# Sheet2.net
KiCad netlist of a schematic drawn in Altium Designer
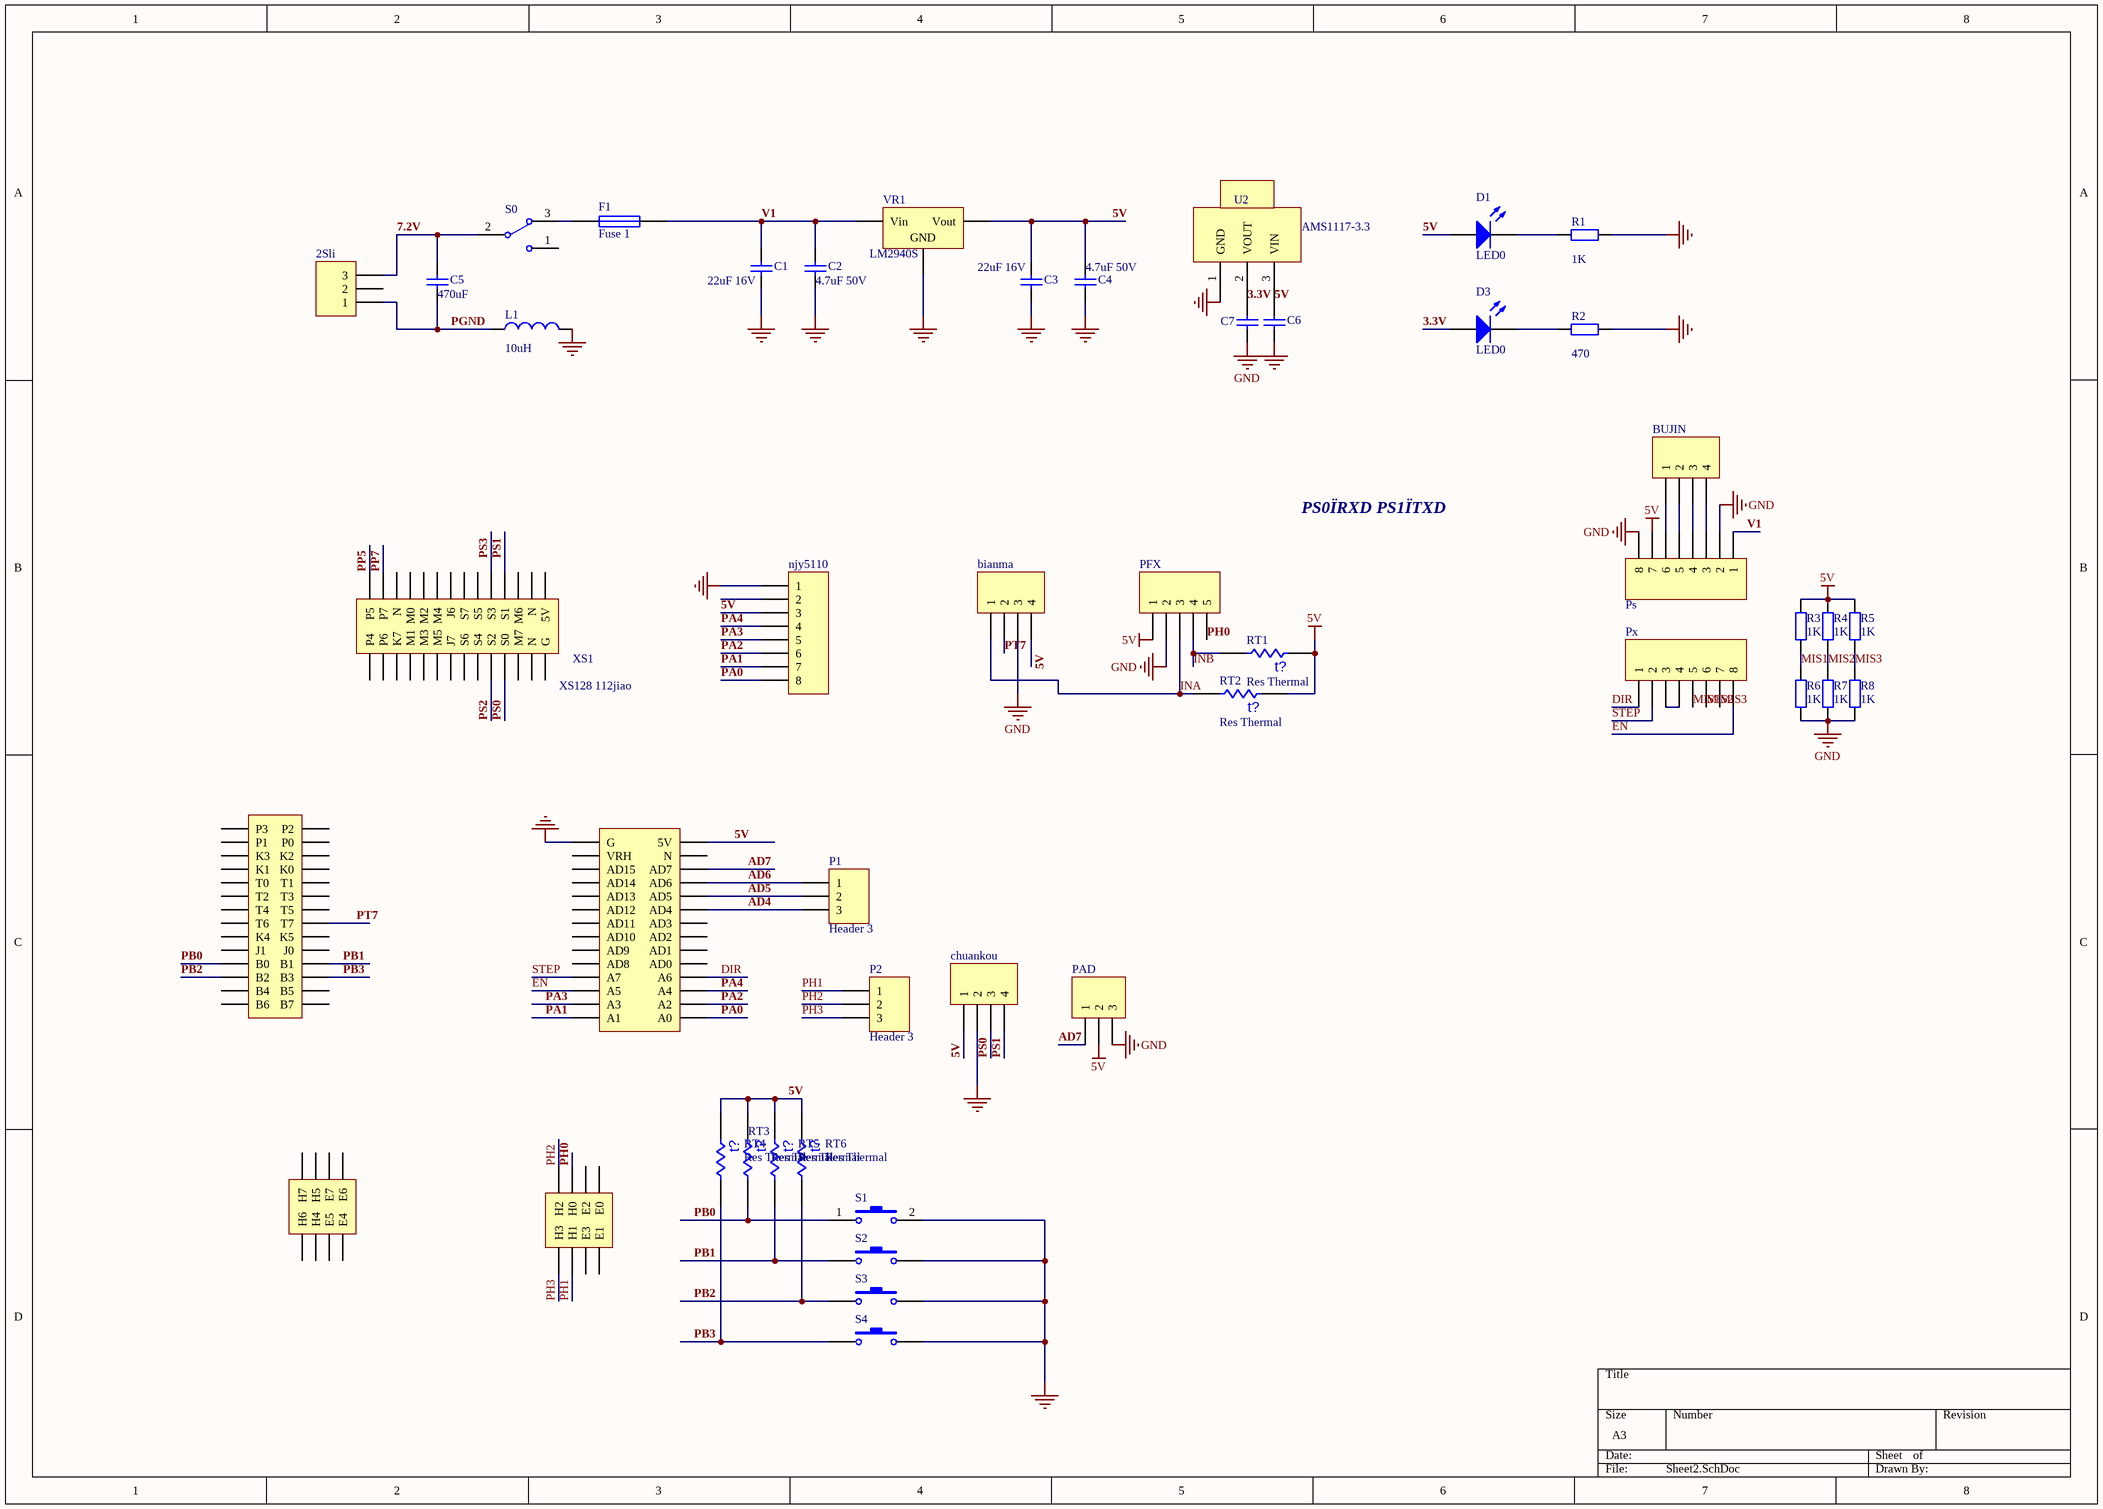
[diagram p0: Sheet2.SchDoc]

(export (version "E")
  (design (tool "Eeschema 10.0.6"))
  (components
    (comp (ref "2Sli")
      (value "Header 3")
      (footprint "HDR1X3")
      (description "Header, 3-Pin")
      (fields (field (name "PUBLISHER") "Altium Limited"))
      (libsource (lib "Miscellaneous Connectors") (part "Header 3"))
    )
    (comp (ref "bianma")
      (value "Header 4")
      (footprint "HDR1X4")
      (description "Header, 4-Pin")
      (fields (field (name "PUBLISHER") "Altium Limited"))
      (libsource (lib "Miscellaneous Connectors") (part "Header 4"))
    )
    (comp (ref "BUJIN")
      (value "Header 4")
      (footprint "HDR1X4")
      (description "Header, 4-Pin")
      (fields (field (name "PUBLISHER") "Altium Limited"))
      (libsource (lib "Miscellaneous Connectors") (part "Header 4"))
    )
    (comp (ref "C1")
      (value "22uF 16V")
      (footprint "C1206")
      (description "Capacitor")
      (fields (field (name "Comment") "Cap") (field (name "PUBLISHER") "Altium Limited"))
      (libsource (lib "Miscellaneous Devices") (part "Cap"))
    )
    (comp (ref "C2")
      (value "4.7uF 50V")
      (footprint "C0805")
      (description "Capacitor")
      (fields (field (name "Comment") "Cap") (field (name "PUBLISHER") "Altium Limited"))
      (libsource (lib "Miscellaneous Devices") (part "Cap"))
    )
    (comp (ref "C3")
      (value "22uF 16V")
      (footprint "C0805")
      (description "Capacitor")
      (fields (field (name "Comment") "Cap") (field (name "PUBLISHER") "Altium Limited"))
      (libsource (lib "Miscellaneous Devices") (part "Cap"))
    )
    (comp (ref "C4")
      (value "4.7uF 50V")
      (footprint "C1206")
      (description "Capacitor")
      (fields (field (name "Comment") "Cap") (field (name "PUBLISHER") "Altium Limited"))
      (libsource (lib "Miscellaneous Devices") (part "Cap"))
    )
    (comp (ref "C5")
      (value "470uF")
      (footprint "C3")
      (description "Capacitor")
      (fields (field (name "Comment") "Cap") (field (name "PUBLISHER") "Altium Limited"))
      (libsource (lib "Miscellaneous Devices") (part "Cap"))
    )
    (comp (ref "C6")
      (value "Cap")
      (footprint "C0805")
      (description "Capacitor")
      (fields (field (name "PUBLISHER") "Altium Limited"))
      (libsource (lib "Miscellaneous Devices") (part "Cap"))
    )
    (comp (ref "C7")
      (value "Cap")
      (footprint "C0805")
      (description "Capacitor")
      (fields (field (name "PUBLISHER") "Altium Limited"))
      (libsource (lib "Miscellaneous Devices") (part "Cap"))
    )
    (comp (ref "chuankou")
      (value "Header 4")
      (footprint "HDR1X4")
      (description "Header, 4-Pin")
      (fields (field (name "PUBLISHER") "Altium Limited"))
      (libsource (lib "Miscellaneous Connectors") (part "Header 4"))
    )
    (comp (ref "D1")
      (value "LED0")
      (footprint "C0805")
      (description "Typical INFRARED GaAs LED")
      (fields (field (name "PUBLISHER") "Altium Limited"))
      (libsource (lib "Miscellaneous Devices") (part "LED0"))
    )
    (comp (ref "D3")
      (value "LED0")
      (footprint "C0805")
      (description "Typical INFRARED GaAs LED")
      (fields (field (name "PUBLISHER") "Altium Limited"))
      (libsource (lib "Miscellaneous Devices") (part "LED0"))
    )
    (comp (ref "F1")
      (value "Fuse 1")
      (footprint "FUSE")
      (description "2A")
      (fields (field (name "PUBLISHER") "Altium Limited"))
      (libsource (lib "Miscellaneous Devices") (part "Fuse 1"))
    )
    (comp (ref "L1")
      (value "10uH")
      (footprint "L")
      (description "Inductor")
      (fields (field (name "PUBLISHER") "Altium Limited"))
      (libsource (lib "Miscellaneous Devices") (part "Inductor"))
    )
    (comp (ref "njy5110")
      (value "Header 8")
      (footprint "HDR1X8")
      (description "Header, 8-Pin")
      (fields (field (name "PUBLISHER") "Altium Limited"))
      (libsource (lib "") (part "Header 8_2"))
    )
    (comp (ref "P1")
      (value "Header 3")
      (footprint "HDR1X3")
      (description "Header, 3-Pin")
      (fields (field (name "PUBLISHER") "Altium Limited"))
      (libsource (lib "") (part "Header 3_1"))
    )
    (comp (ref "P2")
      (value "Header 3")
      (footprint "HDR1X3")
      (description "Header, 3-Pin")
      (fields (field (name "PUBLISHER") "Altium Limited"))
      (libsource (lib "") (part "Header 3_1"))
    )
    (comp (ref "PAD")
      (value "Header 3")
      (footprint "HDR1X3")
      (description "Header, 3-Pin")
      (fields (field (name "PUBLISHER") "Altium Limited"))
      (libsource (lib "") (part "Header 3_2"))
    )
    (comp (ref "PFX")
      (value "Header 5")
      (footprint "HDR1X5")
      (description "Header, 5-Pin")
      (fields (field (name "PUBLISHER") "Altium Limited"))
      (libsource (lib "Miscellaneous Connectors") (part "Header 5"))
    )
    (comp (ref "Ps")
      (value "Header 8")
      (footprint "HDR1X8")
      (description "Header, 8-Pin")
      (fields (field (name "PUBLISHER") "Altium Limited"))
      (libsource (lib "Miscellaneous Connectors") (part "Header 8"))
    )
    (comp (ref "Px")
      (value "Header 8")
      (footprint "HDR1X8")
      (description "Header, 8-Pin")
      (fields (field (name "PUBLISHER") "Altium Limited"))
      (libsource (lib "") (part "Header 8_1"))
    )
    (comp (ref "R1")
      (value "1K")
      (footprint "C0805")
      (description "Resistor")
      (fields (field (name "Comment") "Res2") (field (name "PUBLISHER") "Altium Limited"))
      (libsource (lib "") (part "Res2_1"))
    )
    (comp (ref "R2")
      (value "470")
      (footprint "C0805")
      (description "Resistor")
      (fields (field (name "Comment") "Res2") (field (name "PUBLISHER") "Altium Limited"))
      (libsource (lib "") (part "Res2_1"))
    )
    (comp (ref "R3")
      (value "1K")
      (footprint "C0805")
      (description "Resistor")
      (fields (field (name "Comment") "Res2") (field (name "PUBLISHER") "Altium Limited"))
      (libsource (lib "Miscellaneous Devices") (part "Res2"))
    )
    (comp (ref "R4")
      (value "1K")
      (footprint "C0805")
      (description "Resistor")
      (fields (field (name "Comment") "Res2") (field (name "PUBLISHER") "Altium Limited"))
      (libsource (lib "Miscellaneous Devices") (part "Res2"))
    )
    (comp (ref "R5")
      (value "1K")
      (footprint "C0805")
      (description "Resistor")
      (fields (field (name "Comment") "Res2") (field (name "PUBLISHER") "Altium Limited"))
      (libsource (lib "Miscellaneous Devices") (part "Res2"))
    )
    (comp (ref "R6")
      (value "1K")
      (footprint "C0805")
      (description "Resistor")
      (fields (field (name "Comment") "Res2") (field (name "PUBLISHER") "Altium Limited"))
      (libsource (lib "Miscellaneous Devices") (part "Res2"))
    )
    (comp (ref "R7")
      (value "1K")
      (footprint "C0805")
      (description "Resistor")
      (fields (field (name "Comment") "Res2") (field (name "PUBLISHER") "Altium Limited"))
      (libsource (lib "Miscellaneous Devices") (part "Res2"))
    )
    (comp (ref "R8")
      (value "1K")
      (footprint "C0805")
      (description "Resistor")
      (fields (field (name "Comment") "Res2") (field (name "PUBLISHER") "Altium Limited"))
      (libsource (lib "Miscellaneous Devices") (part "Res2"))
    )
    (comp (ref "RT1")
      (value "Res Thermal")
      (footprint "6-0805")
      (description "Thermistor")
      (fields (field (name "PUBLISHER") "Altium Limited"))
      (libsource (lib "Miscellaneous Devices") (part "Res Thermal"))
    )
    (comp (ref "RT2")
      (value "Res Thermal")
      (footprint "6-0805")
      (description "Thermistor")
      (fields (field (name "PUBLISHER") "Altium Limited"))
      (libsource (lib "Miscellaneous Devices") (part "Res Thermal"))
    )
    (comp (ref "RT3")
      (value "Res Thermal")
      (footprint "6-0805")
      (description "Thermistor")
      (fields (field (name "PUBLISHER") "Altium Limited"))
      (libsource (lib "Miscellaneous Devices") (part "Res Thermal"))
    )
    (comp (ref "RT4")
      (value "Res Thermal")
      (footprint "6-0805")
      (description "Thermistor")
      (fields (field (name "PUBLISHER") "Altium Limited"))
      (libsource (lib "Miscellaneous Devices") (part "Res Thermal"))
    )
    (comp (ref "RT5")
      (value "Res Thermal")
      (footprint "6-0805")
      (description "Thermistor")
      (fields (field (name "PUBLISHER") "Altium Limited"))
      (libsource (lib "Miscellaneous Devices") (part "Res Thermal"))
    )
    (comp (ref "RT6")
      (value "Res Thermal")
      (footprint "6-0805")
      (description "Thermistor")
      (fields (field (name "PUBLISHER") "Altium Limited"))
      (libsource (lib "Miscellaneous Devices") (part "Res Thermal"))
    )
    (comp (ref "S0")
      (value "SW-SPDT")
      (footprint "S4")
      (description "SPDT Subminiature Toggle Switch, Right Angle Mounting, Vertical Actuation")
      (fields (field (name "PUBLISHER") "Altium Limited"))
      (libsource (lib "Miscellaneous Devices") (part "SW-SPDT"))
    )
    (comp (ref "S1")
      (value "SW-PB")
      (footprint "S5")
      (description "Switch")
      (fields (field (name "PUBLISHER") "Altium Limited"))
      (libsource (lib "") (part "SW-PB_1"))
    )
    (comp (ref "S2")
      (value "SW-PB")
      (footprint "S5")
      (description "Switch")
      (fields (field (name "PUBLISHER") "Altium Limited"))
      (libsource (lib "Miscellaneous Devices") (part "SW-PB"))
    )
    (comp (ref "S3")
      (value "SW-PB")
      (footprint "S5")
      (description "Switch")
      (fields (field (name "PUBLISHER") "Altium Limited"))
      (libsource (lib "Miscellaneous Devices") (part "SW-PB"))
    )
    (comp (ref "S4")
      (value "SW-PB")
      (footprint "S5")
      (description "Switch")
      (fields (field (name "PUBLISHER") "Altium Limited"))
      (libsource (lib "Miscellaneous Devices") (part "SW-PB"))
    )
    (comp (ref "U2") (value "AMS1117-3.3") (footprint "SOT223") (libsource (lib "*") (part "AMS1117-3.3")))
    (comp (ref "VR1")
      (value "LM2940S")
      (footprint "LM2940")
      (description "Voltage Regulator")
      (fields (field (name "PUBLISHER") "Altium Limited"))
      (libsource (lib "Miscellaneous Devices") (part "Volt Reg"))
    )
    (comp (ref "XS1")
      (value "XS128 112jiao")
      (footprint "XS128接口")
      (libsource (lib "PCB_Project2") (part "XS128 112jiao"))
    )
  )
  (nets
    (net (code "1") (name "/3.3V") (class "Default")
      (node (ref "C7") (pin "2") (pinfunction "2_2") (pintype "passive"))
      (node (ref "D3") (pin "1") (pinfunction "A_1") (pintype "passive"))
      (node (ref "U2") (pin "2") (pinfunction "VOUT_2") (pintype "passive"))
    )
    (net (code "2") (name "/7.2V") (class "Default")
      (node (ref "2Sli") (pin "3") (pinfunction "3_3") (pintype "passive"))
      (node (ref "C5") (pin "2") (pinfunction "2_2") (pintype "passive"))
      (node (ref "S0") (pin "2") (pinfunction "2_2") (pintype "passive"))
    )
    (net (code "3") (name "/AD4") (class "Default")
      (node (ref "P1") (pin "3") (pinfunction "3_3") (pintype "passive"))
      (node (ref "XS1") (pin "317") (pinfunction "AD4_317") (pintype "passive"))
    )
    (net (code "4") (name "/AD5") (class "Default")
      (node (ref "P1") (pin "2") (pinfunction "2_2") (pintype "passive"))
      (node (ref "XS1") (pin "319") (pinfunction "AD5_319") (pintype "passive"))
    )
    (net (code "5") (name "/AD6") (class "Default")
      (node (ref "P1") (pin "1") (pinfunction "1_1") (pintype "passive"))
      (node (ref "XS1") (pin "321") (pinfunction "AD6_321") (pintype "passive"))
    )
    (net (code "6") (name "/AD7") (class "Default")
      (node (ref "PAD") (pin "1") (pinfunction "1_1") (pintype "passive"))
      (node (ref "XS1") (pin "323") (pinfunction "AD7_323") (pintype "passive"))
    )
    (net (code "7") (name "/DIR") (class "Default")
      (node (ref "Px") (pin "1") (pinfunction "1_1") (pintype "passive"))
      (node (ref "XS1") (pin "307") (pinfunction "A6_307") (pintype "passive"))
    )
    (net (code "8") (name "/EN") (class "Default")
      (node (ref "Px") (pin "8") (pinfunction "8_8") (pintype "passive"))
      (node (ref "XS1") (pin "306") (pinfunction "A5_306") (pintype "passive"))
    )
    (net (code "9") (name "/INA") (class "Default")
      (node (ref "PFX") (pin "3") (pinfunction "3_3") (pintype "passive"))
      (node (ref "RT2") (pin "2") (pinfunction "2_2") (pintype "passive"))
      (node (ref "bianma") (pin "1") (pinfunction "1_1") (pintype "passive"))
    )
    (net (code "10") (name "/INB") (class "Default")
      (node (ref "PFX") (pin "4") (pinfunction "4_4") (pintype "passive"))
      (node (ref "RT1") (pin "2") (pinfunction "2_2") (pintype "passive"))
    )
    (net (code "11") (name "/MIS1") (class "Default")
      (node (ref "Px") (pin "5") (pinfunction "5_5") (pintype "passive"))
      (node (ref "R3") (pin "1") (pinfunction "1_1") (pintype "passive"))
      (node (ref "R6") (pin "2") (pinfunction "2_2") (pintype "passive"))
    )
    (net (code "12") (name "/MIS2") (class "Default")
      (node (ref "Px") (pin "6") (pinfunction "6_6") (pintype "passive"))
      (node (ref "R4") (pin "1") (pinfunction "1_1") (pintype "passive"))
      (node (ref "R7") (pin "2") (pinfunction "2_2") (pintype "passive"))
    )
    (net (code "13") (name "/MIS3") (class "Default")
      (node (ref "Px") (pin "7") (pinfunction "7_7") (pintype "passive"))
      (node (ref "R5") (pin "1") (pinfunction "1_1") (pintype "passive"))
      (node (ref "R8") (pin "2") (pinfunction "2_2") (pintype "passive"))
    )
    (net (code "14") (name "/PA0") (class "Default")
      (node (ref "XS1") (pin "301") (pinfunction "A0_301") (pintype "passive"))
      (node (ref "njy5110") (pin "8") (pinfunction "8_8") (pintype "passive"))
    )
    (net (code "15") (name "/PA1") (class "Default")
      (node (ref "XS1") (pin "302") (pinfunction "A1_302") (pintype "passive"))
      (node (ref "njy5110") (pin "7") (pinfunction "7_7") (pintype "passive"))
    )
    (net (code "16") (name "/PA2") (class "Default")
      (node (ref "XS1") (pin "303") (pinfunction "A2_303") (pintype "passive"))
      (node (ref "njy5110") (pin "6") (pinfunction "6_6") (pintype "passive"))
    )
    (net (code "17") (name "/PA3") (class "Default")
      (node (ref "XS1") (pin "304") (pinfunction "A3_304") (pintype "passive"))
      (node (ref "njy5110") (pin "5") (pinfunction "5_5") (pintype "passive"))
    )
    (net (code "18") (name "/PA4") (class "Default")
      (node (ref "XS1") (pin "305") (pinfunction "A4_305") (pintype "passive"))
      (node (ref "njy5110") (pin "4") (pinfunction "4_4") (pintype "passive"))
    )
    (net (code "19") (name "/PB0") (class "Default")
      (node (ref "RT3") (pin "2") (pinfunction "2_2") (pintype "passive"))
      (node (ref "S1") (pin "1") (pinfunction "1_1") (pintype "passive"))
      (node (ref "XS1") (pin "121") (pinfunction "B0_121") (pintype "passive"))
    )
    (net (code "20") (name "/PB1") (class "Default")
      (node (ref "RT5") (pin "2") (pinfunction "2_2") (pintype "passive"))
      (node (ref "S2") (pin "1") (pinfunction "1_1") (pintype "passive"))
      (node (ref "XS1") (pin "122") (pinfunction "B1_122") (pintype "passive"))
    )
    (net (code "21") (name "/PB2") (class "Default")
      (node (ref "RT6") (pin "2") (pinfunction "2_2") (pintype "passive"))
      (node (ref "S3") (pin "1") (pinfunction "1_1") (pintype "passive"))
      (node (ref "XS1") (pin "123") (pinfunction "B2_123") (pintype "passive"))
    )
    (net (code "22") (name "/PB3") (class "Default")
      (node (ref "RT4") (pin "2") (pinfunction "2_2") (pintype "passive"))
      (node (ref "S4") (pin "1") (pinfunction "1_1") (pintype "passive"))
      (node (ref "XS1") (pin "124") (pinfunction "B3_124") (pintype "passive"))
    )
    (net (code "23") (name "/PGND") (class "Default")
      (node (ref "2Sli") (pin "1") (pinfunction "1_1") (pintype "passive"))
      (node (ref "C5") (pin "1") (pinfunction "1_1") (pintype "passive"))
      (node (ref "L1") (pin "1") (pinfunction "1_1") (pintype "passive"))
    )
    (net (code "24") (name "/PH0") (class "Default")
      (node (ref "PFX") (pin "5") (pinfunction "5_5") (pintype "passive"))
      (node (ref "XS1") (pin "504") (pinfunction "H0_504") (pintype "passive"))
    )
    (net (code "25") (name "/PH1") (class "Default")
      (node (ref "P2") (pin "1") (pinfunction "1_1") (pintype "passive"))
      (node (ref "XS1") (pin "503") (pinfunction "H1_503") (pintype "passive"))
    )
    (net (code "26") (name "/PH2") (class "Default")
      (node (ref "P2") (pin "2") (pinfunction "2_2") (pintype "passive"))
      (node (ref "XS1") (pin "502") (pinfunction "H2_502") (pintype "passive"))
    )
    (net (code "27") (name "/PH3") (class "Default")
      (node (ref "P2") (pin "3") (pinfunction "3_3") (pintype "passive"))
      (node (ref "XS1") (pin "501") (pinfunction "H3_501") (pintype "passive"))
    )
    (net (code "28") (name "/PP5") (class "Default")
      (node (ref "XS1") (pin "227") (pinfunction "P5_227") (pintype "passive"))
    )
    (net (code "29") (name "/PP7") (class "Default")
      (node (ref "XS1") (pin "225") (pinfunction "P7_225") (pintype "passive"))
    )
    (net (code "30") (name "/PS0") (class "Default")
      (node (ref "XS1") (pin "208") (pinfunction "S0_208") (pintype "passive"))
      (node (ref "chuankou") (pin "3") (pinfunction "3_3") (pintype "passive"))
    )
    (net (code "31") (name "/PS1") (class "Default")
      (node (ref "XS1") (pin "207") (pinfunction "S1_207") (pintype "passive"))
      (node (ref "chuankou") (pin "4") (pinfunction "4_4") (pintype "passive"))
    )
    (net (code "32") (name "/PS2") (class "Default")
      (node (ref "XS1") (pin "210") (pinfunction "S2_210") (pintype "passive"))
    )
    (net (code "33") (name "/PS3") (class "Default")
      (node (ref "XS1") (pin "209") (pinfunction "S3_209") (pintype "passive"))
    )
    (net (code "34") (name "/PT7") (class "Default")
      (node (ref "XS1") (pin "116") (pinfunction "T7_116") (pintype "passive"))
      (node (ref "bianma") (pin "2") (pinfunction "2_2") (pintype "passive"))
    )
    (net (code "35") (name "/STEP") (class "Default")
      (node (ref "Px") (pin "2") (pinfunction "2_2") (pintype "passive"))
      (node (ref "XS1") (pin "308") (pinfunction "A7_308") (pintype "passive"))
    )
    (net (code "36") (name "/V1") (class "Default")
      (node (ref "C1") (pin "2") (pinfunction "2_2") (pintype "passive"))
      (node (ref "C2") (pin "2") (pinfunction "2_2") (pintype "passive"))
      (node (ref "F1") (pin "2") (pinfunction "2_2") (pintype "passive"))
      (node (ref "Ps") (pin "1") (pinfunction "1_1") (pintype "passive"))
      (node (ref "VR1") (pin "1") (pinfunction "Vin_1") (pintype "passive"))
    )
    (net (code "37") (name "5V") (class "Default")
      (node (ref "C3") (pin "2") (pinfunction "2_2") (pintype "passive"))
      (node (ref "C4") (pin "2") (pinfunction "2_2") (pintype "passive"))
      (node (ref "C6") (pin "1") (pinfunction "1_1") (pintype "passive"))
      (node (ref "D1") (pin "1") (pinfunction "A_1") (pintype "passive"))
      (node (ref "PAD") (pin "2") (pinfunction "2_2") (pintype "passive"))
      (node (ref "PFX") (pin "1") (pinfunction "1_1") (pintype "passive"))
      (node (ref "Ps") (pin "7") (pinfunction "7_7") (pintype "passive"))
      (node (ref "R3") (pin "2") (pinfunction "2_2") (pintype "passive"))
      (node (ref "R4") (pin "2") (pinfunction "2_2") (pintype "passive"))
      (node (ref "R5") (pin "2") (pinfunction "2_2") (pintype "passive"))
      (node (ref "RT1") (pin "1") (pinfunction "1_1") (pintype "passive"))
      (node (ref "RT2") (pin "1") (pinfunction "1_1") (pintype "passive"))
      (node (ref "RT3") (pin "1") (pinfunction "1_1") (pintype "passive"))
      (node (ref "RT4") (pin "1") (pinfunction "1_1") (pintype "passive"))
      (node (ref "RT5") (pin "1") (pinfunction "1_1") (pintype "passive"))
      (node (ref "RT6") (pin "1") (pinfunction "1_1") (pintype "passive"))
      (node (ref "U2") (pin "3") (pinfunction "VIN_3") (pintype "passive"))
      (node (ref "VR1") (pin "3") (pinfunction "Vout_3") (pintype "passive"))
      (node (ref "XS1") (pin "327") (pinfunction "5V_327") (pintype "passive"))
      (node (ref "bianma") (pin "4") (pinfunction "4_4") (pintype "passive"))
      (node (ref "chuankou") (pin "1") (pinfunction "1_1") (pintype "passive"))
      (node (ref "njy5110") (pin "3") (pinfunction "3_3") (pintype "passive"))
    )
    (net (code "38") (name "GND") (class "Default")
      (node (ref "C1") (pin "1") (pinfunction "1_1") (pintype "passive"))
      (node (ref "C2") (pin "1") (pinfunction "1_1") (pintype "passive"))
      (node (ref "C3") (pin "1") (pinfunction "1_1") (pintype "passive"))
      (node (ref "C4") (pin "1") (pinfunction "1_1") (pintype "passive"))
      (node (ref "C6") (pin "2") (pinfunction "2_2") (pintype "passive"))
      (node (ref "C7") (pin "1") (pinfunction "1_1") (pintype "passive"))
      (node (ref "L1") (pin "2") (pinfunction "2_2") (pintype "passive"))
      (node (ref "PAD") (pin "3") (pinfunction "3_3") (pintype "passive"))
      (node (ref "PFX") (pin "2") (pinfunction "2_2") (pintype "passive"))
      (node (ref "Ps") (pin "2") (pinfunction "2_2") (pintype "passive"))
      (node (ref "Ps") (pin "8") (pinfunction "8_8") (pintype "passive"))
      (node (ref "R1") (pin "2") (pinfunction "2_2") (pintype "passive"))
      (node (ref "R2") (pin "2") (pinfunction "2_2") (pintype "passive"))
      (node (ref "R6") (pin "1") (pinfunction "1_1") (pintype "passive"))
      (node (ref "R7") (pin "1") (pinfunction "1_1") (pintype "passive"))
      (node (ref "R8") (pin "1") (pinfunction "1_1") (pintype "passive"))
      (node (ref "S1") (pin "2") (pinfunction "2_2") (pintype "passive"))
      (node (ref "S2") (pin "2") (pinfunction "2_2") (pintype "passive"))
      (node (ref "S3") (pin "2") (pinfunction "2_2") (pintype "passive"))
      (node (ref "S4") (pin "2") (pinfunction "2_2") (pintype "passive"))
      (node (ref "U2") (pin "1") (pinfunction "GND_1") (pintype "passive"))
      (node (ref "VR1") (pin "2") (pinfunction "GND_2") (pintype "passive"))
      (node (ref "XS1") (pin "328") (pinfunction "G_328") (pintype "passive"))
      (node (ref "bianma") (pin "3") (pinfunction "3_3") (pintype "passive"))
      (node (ref "chuankou") (pin "2") (pinfunction "2_2") (pintype "passive"))
      (node (ref "njy5110") (pin "1") (pinfunction "1_1") (pintype "passive"))
    )
    (net (code "39") (name "Net-(BUJIN-Pad1)") (class "Default")
      (node (ref "BUJIN") (pin "1") (pinfunction "1_1") (pintype "passive"))
      (node (ref "Ps") (pin "6") (pinfunction "6_6") (pintype "passive"))
    )
    (net (code "40") (name "Net-(BUJIN-Pad2)") (class "Default")
      (node (ref "BUJIN") (pin "2") (pinfunction "2_2") (pintype "passive"))
      (node (ref "Ps") (pin "5") (pinfunction "5_5") (pintype "passive"))
    )
    (net (code "41") (name "Net-(BUJIN-Pad3)") (class "Default")
      (node (ref "BUJIN") (pin "3") (pinfunction "3_3") (pintype "passive"))
      (node (ref "Ps") (pin "4") (pinfunction "4_4") (pintype "passive"))
    )
    (net (code "42") (name "Net-(BUJIN-Pad4)") (class "Default")
      (node (ref "BUJIN") (pin "4") (pinfunction "4_4") (pintype "passive"))
      (node (ref "Ps") (pin "3") (pinfunction "3_3") (pintype "passive"))
    )
    (net (code "43") (name "Net-(D1-K)") (class "Default")
      (node (ref "D1") (pin "2") (pinfunction "K_2") (pintype "passive"))
      (node (ref "R1") (pin "1") (pinfunction "1_1") (pintype "passive"))
    )
    (net (code "44") (name "Net-(D3-K)") (class "Default")
      (node (ref "D3") (pin "2") (pinfunction "K_2") (pintype "passive"))
      (node (ref "R2") (pin "1") (pinfunction "1_1") (pintype "passive"))
    )
    (net (code "45") (name "Net-(F1-Pad1)") (class "Default")
      (node (ref "F1") (pin "1") (pinfunction "1_1") (pintype "passive"))
      (node (ref "S0") (pin "3") (pinfunction "3_3") (pintype "passive"))
    )
    (net (code "46") (name "Net-(Px-Pad3)") (class "Default")
      (node (ref "Px") (pin "3") (pinfunction "3_3") (pintype "passive"))
      (node (ref "Px") (pin "4") (pinfunction "4_4") (pintype "passive"))
    )
    (net (code "47") (name "unconnected-(2Sli-Pad2)") (class "Default")
      (node (ref "2Sli") (pin "2") (pinfunction "2_2") (pintype "passive"))
    )
    (net (code "48") (name "unconnected-(S0-Pad1)") (class "Default")
      (node (ref "S0") (pin "1") (pinfunction "1_1") (pintype "passive"))
    )
    (net (code "49") (name "unconnected-(XS1-5V-Pad201)") (class "Default")
      (node (ref "XS1") (pin "201") (pinfunction "5V_201") (pintype "passive"))
    )
    (net (code "50") (name "unconnected-(XS1-AD0-Pad309)") (class "Default")
      (node (ref "XS1") (pin "309") (pinfunction "AD0_309") (pintype "passive"))
    )
    (net (code "51") (name "unconnected-(XS1-AD1-Pad311)") (class "Default")
      (node (ref "XS1") (pin "311") (pinfunction "AD1_311") (pintype "passive"))
    )
    (net (code "52") (name "unconnected-(XS1-AD2-Pad313)") (class "Default")
      (node (ref "XS1") (pin "313") (pinfunction "AD2_313") (pintype "passive"))
    )
    (net (code "53") (name "unconnected-(XS1-AD3-Pad315)") (class "Default")
      (node (ref "XS1") (pin "315") (pinfunction "AD3_315") (pintype "passive"))
    )
    (net (code "54") (name "unconnected-(XS1-AD8-Pad310)") (class "Default")
      (node (ref "XS1") (pin "310") (pinfunction "AD8_310") (pintype "passive"))
    )
    (net (code "55") (name "unconnected-(XS1-AD9-Pad312)") (class "Default")
      (node (ref "XS1") (pin "312") (pinfunction "AD9_312") (pintype "passive"))
    )
    (net (code "56") (name "unconnected-(XS1-AD10-Pad314)") (class "Default")
      (node (ref "XS1") (pin "314") (pinfunction "AD10_314") (pintype "passive"))
    )
    (net (code "57") (name "unconnected-(XS1-AD11-Pad316)") (class "Default")
      (node (ref "XS1") (pin "316") (pinfunction "AD11_316") (pintype "passive"))
    )
    (net (code "58") (name "unconnected-(XS1-AD12-Pad318)") (class "Default")
      (node (ref "XS1") (pin "318") (pinfunction "AD12_318") (pintype "passive"))
    )
    (net (code "59") (name "unconnected-(XS1-AD13-Pad320)") (class "Default")
      (node (ref "XS1") (pin "320") (pinfunction "AD13_320") (pintype "passive"))
    )
    (net (code "60") (name "unconnected-(XS1-AD14-Pad322)") (class "Default")
      (node (ref "XS1") (pin "322") (pinfunction "AD14_322") (pintype "passive"))
    )
    (net (code "61") (name "unconnected-(XS1-AD15-Pad324)") (class "Default")
      (node (ref "XS1") (pin "324") (pinfunction "AD15_324") (pintype "passive"))
    )
    (net (code "62") (name "unconnected-(XS1-B4-Pad125)") (class "Default")
      (node (ref "XS1") (pin "125") (pinfunction "B4_125") (pintype "passive"))
    )
    (net (code "63") (name "unconnected-(XS1-B5-Pad126)") (class "Default")
      (node (ref "XS1") (pin "126") (pinfunction "B5_126") (pintype "passive"))
    )
    (net (code "64") (name "unconnected-(XS1-B6-Pad127)") (class "Default")
      (node (ref "XS1") (pin "127") (pinfunction "B6_127") (pintype "passive"))
    )
    (net (code "65") (name "unconnected-(XS1-B7-Pad128)") (class "Default")
      (node (ref "XS1") (pin "128") (pinfunction "B7_128") (pintype "passive"))
    )
    (net (code "66") (name "unconnected-(XS1-E0-Pad508)") (class "Default")
      (node (ref "XS1") (pin "508") (pinfunction "E0_508") (pintype "passive"))
    )
    (net (code "67") (name "unconnected-(XS1-E1-Pad507)") (class "Default")
      (node (ref "XS1") (pin "507") (pinfunction "E1_507") (pintype "passive"))
    )
    (net (code "68") (name "unconnected-(XS1-E2-Pad506)") (class "Default")
      (node (ref "XS1") (pin "506") (pinfunction "E2_506") (pintype "passive"))
    )
    (net (code "69") (name "unconnected-(XS1-E3-Pad505)") (class "Default")
      (node (ref "XS1") (pin "505") (pinfunction "E3_505") (pintype "passive"))
    )
    (net (code "70") (name "unconnected-(XS1-E4-Pad407)") (class "Default")
      (node (ref "XS1") (pin "407") (pinfunction "E4_407") (pintype "passive"))
    )
    (net (code "71") (name "unconnected-(XS1-E5-Pad405)") (class "Default")
      (node (ref "XS1") (pin "405") (pinfunction "E5_405") (pintype "passive"))
    )
    (net (code "72") (name "unconnected-(XS1-E6-Pad408)") (class "Default")
      (node (ref "XS1") (pin "408") (pinfunction "E6_408") (pintype "passive"))
    )
    (net (code "73") (name "unconnected-(XS1-E7-Pad406)") (class "Default")
      (node (ref "XS1") (pin "406") (pinfunction "E7_406") (pintype "passive"))
    )
    (net (code "74") (name "unconnected-(XS1-G-Pad202)") (class "Default")
      (node (ref "XS1") (pin "202") (pinfunction "G_202") (pintype "passive"))
    )
    (net (code "75") (name "unconnected-(XS1-H4-Pad403)") (class "Default")
      (node (ref "XS1") (pin "403") (pinfunction "H4_403") (pintype "passive"))
    )
    (net (code "76") (name "unconnected-(XS1-H5-Pad404)") (class "Default")
      (node (ref "XS1") (pin "404") (pinfunction "H5_404") (pintype "passive"))
    )
    (net (code "77") (name "unconnected-(XS1-H6-Pad401)") (class "Default")
      (node (ref "XS1") (pin "401") (pinfunction "H6_401") (pintype "passive"))
    )
    (net (code "78") (name "unconnected-(XS1-H7-Pad402)") (class "Default")
      (node (ref "XS1") (pin "402") (pinfunction "H7_402") (pintype "passive"))
    )
    (net (code "79") (name "unconnected-(XS1-J0-Pad120)") (class "Default")
      (node (ref "XS1") (pin "120") (pinfunction "J0_120") (pintype "passive"))
    )
    (net (code "80") (name "unconnected-(XS1-J1-Pad119)") (class "Default")
      (node (ref "XS1") (pin "119") (pinfunction "J1_119") (pintype "passive"))
    )
    (net (code "81") (name "unconnected-(XS1-J6-Pad215)") (class "Default")
      (node (ref "XS1") (pin "215") (pinfunction "J6_215") (pintype "passive"))
    )
    (net (code "82") (name "unconnected-(XS1-J7-Pad216)") (class "Default")
      (node (ref "XS1") (pin "216") (pinfunction "J7_216") (pintype "passive"))
    )
    (net (code "83") (name "unconnected-(XS1-K0-Pad108)") (class "Default")
      (node (ref "XS1") (pin "108") (pinfunction "K0_108") (pintype "passive"))
    )
    (net (code "84") (name "unconnected-(XS1-K1-Pad107)") (class "Default")
      (node (ref "XS1") (pin "107") (pinfunction "K1_107") (pintype "passive"))
    )
    (net (code "85") (name "unconnected-(XS1-K2-Pad106)") (class "Default")
      (node (ref "XS1") (pin "106") (pinfunction "K2_106") (pintype "passive"))
    )
    (net (code "86") (name "unconnected-(XS1-K3-Pad105)") (class "Default")
      (node (ref "XS1") (pin "105") (pinfunction "K3_105") (pintype "passive"))
    )
    (net (code "87") (name "unconnected-(XS1-K4-Pad117)") (class "Default")
      (node (ref "XS1") (pin "117") (pinfunction "K4_117") (pintype "passive"))
    )
    (net (code "88") (name "unconnected-(XS1-K5-Pad118)") (class "Default")
      (node (ref "XS1") (pin "118") (pinfunction "K5_118") (pintype "passive"))
    )
    (net (code "89") (name "unconnected-(XS1-K7-Pad224)") (class "Default")
      (node (ref "XS1") (pin "224") (pinfunction "K7_224") (pintype "passive"))
    )
    (net (code "90") (name "unconnected-(XS1-M0-Pad221)") (class "Default")
      (node (ref "XS1") (pin "221") (pinfunction "M0_221") (pintype "passive"))
    )
    (net (code "91") (name "unconnected-(XS1-M1-Pad222)") (class "Default")
      (node (ref "XS1") (pin "222") (pinfunction "M1_222") (pintype "passive"))
    )
    (net (code "92") (name "unconnected-(XS1-M2-Pad219)") (class "Default")
      (node (ref "XS1") (pin "219") (pinfunction "M2_219") (pintype "passive"))
    )
    (net (code "93") (name "unconnected-(XS1-M3-Pad220)") (class "Default")
      (node (ref "XS1") (pin "220") (pinfunction "M3_220") (pintype "passive"))
    )
    (net (code "94") (name "unconnected-(XS1-M4-Pad217)") (class "Default")
      (node (ref "XS1") (pin "217") (pinfunction "M4_217") (pintype "passive"))
    )
    (net (code "95") (name "unconnected-(XS1-M5-Pad218)") (class "Default")
      (node (ref "XS1") (pin "218") (pinfunction "M5_218") (pintype "passive"))
    )
    (net (code "96") (name "unconnected-(XS1-M6-Pad205)") (class "Default")
      (node (ref "XS1") (pin "205") (pinfunction "M6_205") (pintype "passive"))
    )
    (net (code "97") (name "unconnected-(XS1-M7-Pad206)") (class "Default")
      (node (ref "XS1") (pin "206") (pinfunction "M7_206") (pintype "passive"))
    )
    (net (code "98") (name "unconnected-(XS1-N-Pad203)") (class "Default")
      (node (ref "XS1") (pin "203") (pinfunction "N_203") (pintype "passive"))
    )
    (net (code "99") (name "unconnected-(XS1-N-Pad204)") (class "Default")
      (node (ref "XS1") (pin "204") (pinfunction "N_204") (pintype "passive"))
    )
    (net (code "100") (name "unconnected-(XS1-N-Pad223)") (class "Default")
      (node (ref "XS1") (pin "223") (pinfunction "N_223") (pintype "passive"))
    )
    (net (code "101") (name "unconnected-(XS1-N-Pad325)") (class "Default")
      (node (ref "XS1") (pin "325") (pinfunction "N_325") (pintype "passive"))
    )
    (net (code "102") (name "unconnected-(XS1-P0-Pad104)") (class "Default")
      (node (ref "XS1") (pin "104") (pinfunction "P0_104") (pintype "passive"))
    )
    (net (code "103") (name "unconnected-(XS1-P1-Pad103)") (class "Default")
      (node (ref "XS1") (pin "103") (pinfunction "P1_103") (pintype "passive"))
    )
    (net (code "104") (name "unconnected-(XS1-P2-Pad102)") (class "Default")
      (node (ref "XS1") (pin "102") (pinfunction "P2_102") (pintype "passive"))
    )
    (net (code "105") (name "unconnected-(XS1-P3-Pad101)") (class "Default")
      (node (ref "XS1") (pin "101") (pinfunction "P3_101") (pintype "passive"))
    )
    (net (code "106") (name "unconnected-(XS1-P4-Pad228)") (class "Default")
      (node (ref "XS1") (pin "228") (pinfunction "P4_228") (pintype "passive"))
    )
    (net (code "107") (name "unconnected-(XS1-P6-Pad226)") (class "Default")
      (node (ref "XS1") (pin "226") (pinfunction "P6_226") (pintype "passive"))
    )
    (net (code "108") (name "unconnected-(XS1-S4-Pad212)") (class "Default")
      (node (ref "XS1") (pin "212") (pinfunction "S4_212") (pintype "passive"))
    )
    (net (code "109") (name "unconnected-(XS1-S5-Pad211)") (class "Default")
      (node (ref "XS1") (pin "211") (pinfunction "S5_211") (pintype "passive"))
    )
    (net (code "110") (name "unconnected-(XS1-S6-Pad214)") (class "Default")
      (node (ref "XS1") (pin "214") (pinfunction "S6_214") (pintype "passive"))
    )
    (net (code "111") (name "unconnected-(XS1-S7-Pad213)") (class "Default")
      (node (ref "XS1") (pin "213") (pinfunction "S7_213") (pintype "passive"))
    )
    (net (code "112") (name "unconnected-(XS1-T0-Pad109)") (class "Default")
      (node (ref "XS1") (pin "109") (pinfunction "T0_109") (pintype "passive"))
    )
    (net (code "113") (name "unconnected-(XS1-T1-Pad110)") (class "Default")
      (node (ref "XS1") (pin "110") (pinfunction "T1_110") (pintype "passive"))
    )
    (net (code "114") (name "unconnected-(XS1-T2-Pad111)") (class "Default")
      (node (ref "XS1") (pin "111") (pinfunction "T2_111") (pintype "passive"))
    )
    (net (code "115") (name "unconnected-(XS1-T3-Pad112)") (class "Default")
      (node (ref "XS1") (pin "112") (pinfunction "T3_112") (pintype "passive"))
    )
    (net (code "116") (name "unconnected-(XS1-T4-Pad113)") (class "Default")
      (node (ref "XS1") (pin "113") (pinfunction "T4_113") (pintype "passive"))
    )
    (net (code "117") (name "unconnected-(XS1-T5-Pad114)") (class "Default")
      (node (ref "XS1") (pin "114") (pinfunction "T5_114") (pintype "passive"))
    )
    (net (code "118") (name "unconnected-(XS1-T6-Pad115)") (class "Default")
      (node (ref "XS1") (pin "115") (pinfunction "T6_115") (pintype "passive"))
    )
    (net (code "119") (name "unconnected-(XS1-VRH-Pad326)") (class "Default")
      (node (ref "XS1") (pin "326") (pinfunction "VRH_326") (pintype "passive"))
    )
    (net (code "120") (name "unconnected-(njy5110-Pad2)") (class "Default")
      (node (ref "njy5110") (pin "2") (pinfunction "2_2") (pintype "passive"))
    )
  )
)
